# RECOVERY_USBC.net
KiCad netlist of a schematic drawn in Altium Designer
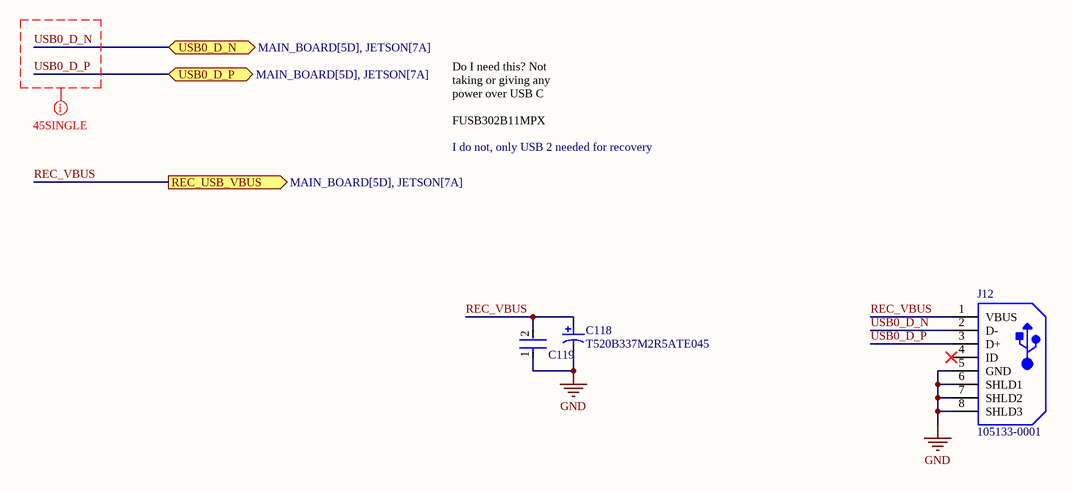
[diagram p0: RECOVERY_USBC.SchDoc]

(export (version "E")
  (design (tool "Eeschema 10.0.6"))
  (components
    (comp (ref "C118")
      (value "T520B337M2R5ATE045")
      (footprint "KEMT-520-B-2_M")
      (description "Tantalum Capacitor, 330 uF, +/- 20%, 2.5 V, -55 to 105 degC, 2-Pin Molded, RoHS, Tape and Reel")
      (libsource (lib "Altium Content Vault") (part "CAP-P-2"))
    )
    (comp (ref "C119")
      (value "C1005X7R1H104K050BB")
      (footprint "FP-C1005-050-0_05-IPC_C")
      (description "Multilayer Ceramic Capacitors 100nF ±10% 50V X7R SMD 0402")
      (fields (field (name "VOLTAGE") "50V") (field (name "TOLERANCE") "10%"))
      (libsource (lib "Altium Content Vault") (part "b4654b650e69147ec39a6b967a45e02"))
    )
    (comp (ref "J12")
      (value "105133-0001")
      (footprint "MOLX-105133-0001_V")
      (description "Micro-USB B Receptacle, Vertical, -30 to 85 degC, 5-Pin SMD, RoHS, Tape and Reel")
      (fields (field (name "MANUFACTURER") "Molex"))
      (libsource (lib "Altium Content Vault") (part "USB-5-3SHLD"))
    )
  )
  (nets
    (net (code "1") (name "/REC_VBUS") (class "Default")
      (node (ref "C118") (pin "1") (pinfunction "1_1") (pintype "passive"))
      (node (ref "C119") (pin "2") (pinfunction "2_2") (pintype "passive"))
      (node (ref "J12") (pin "1") (pinfunction "VBUS_1") (pintype "passive"))
    )
    (net (code "2") (name "/USB0_D_N") (class "Default")
      (node (ref "J12") (pin "2") (pinfunction "D-_2") (pintype "passive"))
    )
    (net (code "3") (name "/USB0_D_P") (class "Default")
      (node (ref "J12") (pin "3") (pinfunction "D+_3") (pintype "passive"))
    )
    (net (code "4") (name "GND") (class "Default")
      (node (ref "C118") (pin "2") (pinfunction "2_2") (pintype "passive"))
      (node (ref "C119") (pin "1") (pinfunction "1_1") (pintype "passive"))
      (node (ref "J12") (pin "5") (pinfunction "GND_5") (pintype "passive"))
      (node (ref "J12") (pin "6") (pinfunction "SHLD1_6") (pintype "passive"))
      (node (ref "J12") (pin "7") (pinfunction "SHLD2_7") (pintype "passive"))
      (node (ref "J12") (pin "8") (pinfunction "SHLD3_8") (pintype "passive"))
    )
    (net (code "5") (name "unconnected-(J12-ID-Pad4)") (class "Default")
      (node (ref "J12") (pin "4") (pinfunction "ID_4") (pintype "passive+no_connect"))
    )
  )
)
